# for_BLDC_fan.net
KiCad netlist of a schematic drawn in Altium Designer
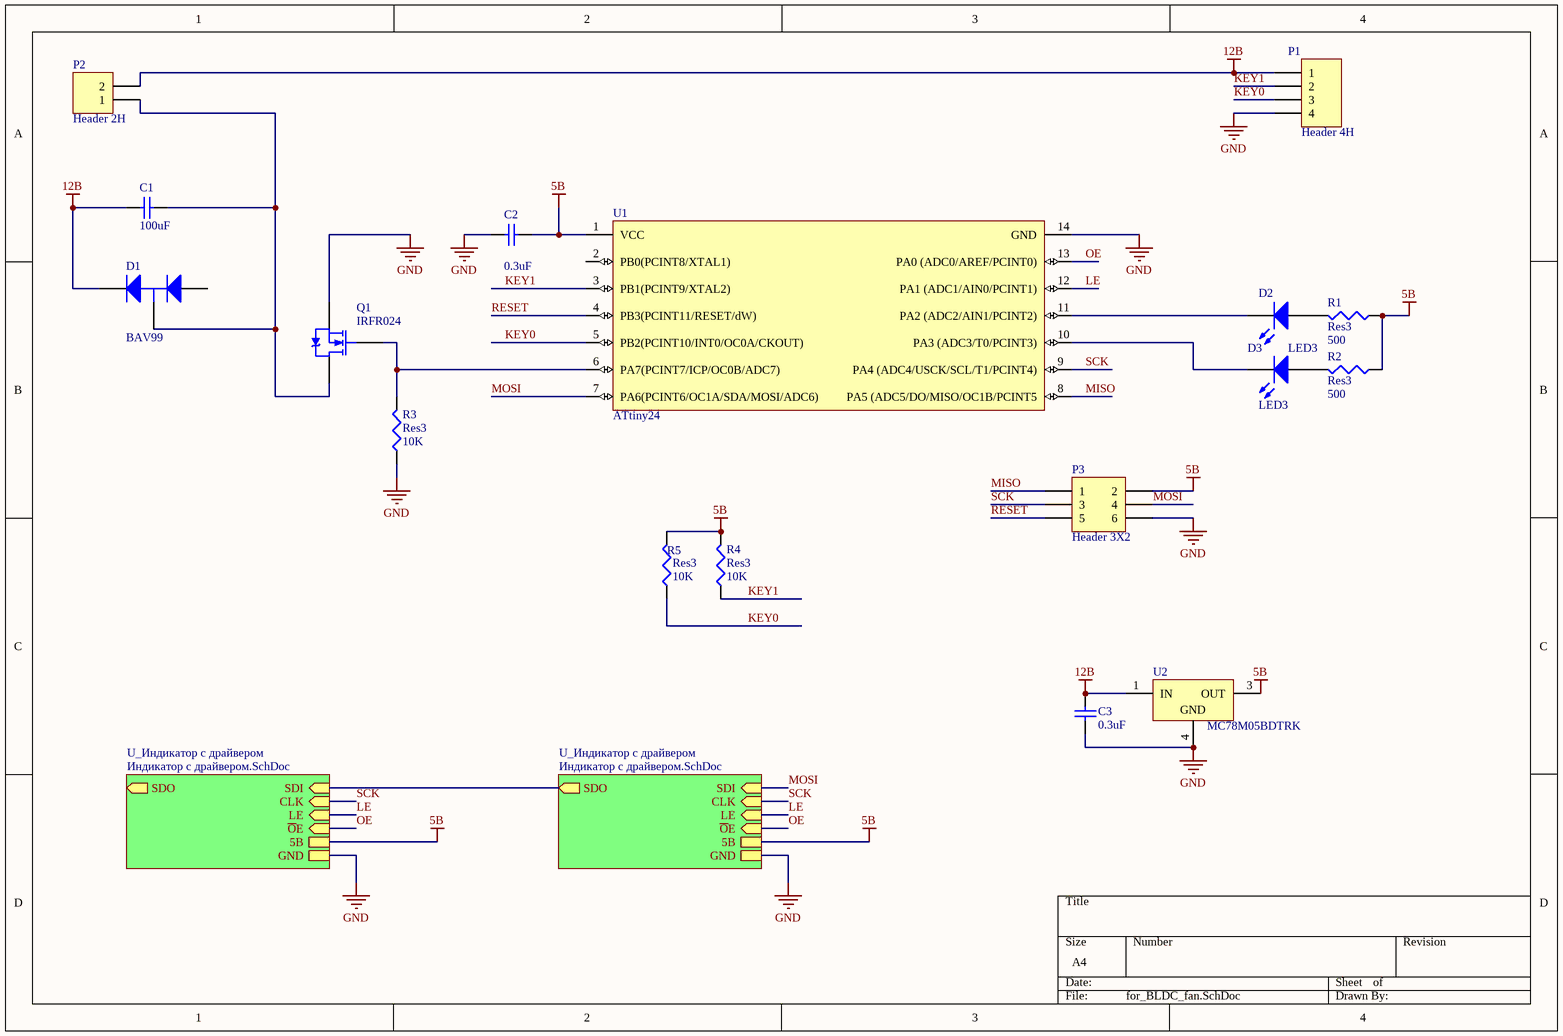
[diagram p0: for_BLDC_fan.SchDoc]

(export (version "E")
  (design (tool "Eeschema 10.0.6"))
  (components
    (comp (ref "C1")
      (value "100uF")
      (footprint "CAPC1608L")
      (description "Capacitor (Semiconductor SIM Model)")
      (fields (field (name "Comment") "Cap Semi") (field (name "PUBLISHER") "Altium Limited"))
      (libsource (lib "Miscellaneous Devices") (part "Cap Semi"))
    )
    (comp (ref "C2")
      (value "0.3uF")
      (footprint "CAPC1608L")
      (description "Capacitor (Semiconductor SIM Model)")
      (fields (field (name "Comment") "Cap Semi") (field (name "PUBLISHER") "Altium Limited"))
      (libsource (lib "Miscellaneous Devices") (part "Cap Semi"))
    )
    (comp (ref "C3")
      (value "0.3uF")
      (footprint "CAPC1608L")
      (description "Capacitor (Semiconductor SIM Model)")
      (fields (field (name "Comment") "Cap Semi") (field (name "PUBLISHER") "Altium Limited"))
      (libsource (lib "Miscellaneous Devices") (part "Cap Semi"))
    )
    (comp (ref "D1")
      (value "BAV99")
      (footprint "SOT-23")
      (description "Silicon Switching Diode Array for High-Speed Switching")
      (fields (field (name "PUBLISHER") "Altium Limited"))
      (libsource (lib "Infineon Discrete Diode") (part "BAV99"))
    )
    (comp (ref "D2")
      (value "LED3")
      (footprint "DSO-C2/D5.6")
      (description "Typical BLUE SiC LED")
      (fields (field (name "PUBLISHER") "Altium Limited"))
      (libsource (lib "Miscellaneous Devices") (part "LED3"))
    )
    (comp (ref "D3")
      (value "LED3")
      (footprint "DSO-C2/D5.6")
      (description "Typical BLUE SiC LED")
      (fields (field (name "PUBLISHER") "Altium Limited"))
      (libsource (lib "Miscellaneous Devices") (part "LED3"))
    )
    (comp (ref "P1")
      (value "Header 4H")
      (footprint "HDR1X4H")
      (description "Header, 4-Pin, Right Angle")
      (fields (field (name "PUBLISHER") "Altium Limited"))
      (libsource (lib "Miscellaneous Connectors") (part "Header 4H"))
    )
    (comp (ref "P2")
      (value "Header 2H")
      (footprint "HDR1X2H")
      (description "Header, 2-Pin, Right Angle")
      (fields (field (name "PUBLISHER") "Altium Limited"))
      (libsource (lib "Miscellaneous Connectors") (part "Header 2H"))
    )
    (comp (ref "P3")
      (value "Header 3X2")
      (footprint "HDR2X3")
      (description "Header, 3-Pin, Dual row")
      (fields (field (name "PUBLISHER") "Altium Limited"))
      (libsource (lib "Miscellaneous Connectors") (part "Header 3X2"))
    )
    (comp (ref "Q1")
      (value "IRFR024")
      (footprint "TO-252AA")
      (description "HEXFET N-Channel Power MOSFET")
      (fields (field (name "PUBLISHER") "Altium Limited"))
      (libsource (lib "IR Discrete MOSFET - Power") (part "IRFR024"))
    )
    (comp (ref "R1")
      (value "Res3")
      (footprint "RESC1608L")
      (description "Resistor")
      (fields (field (name "ALTIUM_VALUE") "500") (field (name "PUBLISHER") "Altium Limited"))
      (libsource (lib "Miscellaneous Devices") (part "Res3"))
    )
    (comp (ref "R2")
      (value "Res3")
      (footprint "RESC1608L")
      (description "Resistor")
      (fields (field (name "ALTIUM_VALUE") "500") (field (name "PUBLISHER") "Altium Limited"))
      (libsource (lib "Miscellaneous Devices") (part "Res3"))
    )
    (comp (ref "R3")
      (value "Res3")
      (footprint "RESC1608L")
      (description "Resistor")
      (fields (field (name "ALTIUM_VALUE") "10K") (field (name "PUBLISHER") "Altium Limited"))
      (libsource (lib "Miscellaneous Devices") (part "Res3"))
    )
    (comp (ref "R4")
      (value "Res3")
      (footprint "RESC1608L")
      (description "Resistor")
      (fields (field (name "ALTIUM_VALUE") "10K") (field (name "PUBLISHER") "Altium Limited"))
      (libsource (lib "Miscellaneous Devices") (part "Res3"))
    )
    (comp (ref "R5")
      (value "Res3")
      (footprint "RESC1608L")
      (description "Resistor")
      (fields (field (name "ALTIUM_VALUE") "10K") (field (name "PUBLISHER") "Altium Limited"))
      (libsource (lib "Miscellaneous Devices") (part "Res3"))
    )
    (comp (ref "U1")
      (value "ATtiny24")
      (footprint "SOIC14_M")
      (description "8-Bit AVR Microcontroller with 1K Byte of Flash Memory")
      (fields (field (name "PUBLISHER") "Altium Limited"))
      (libsource (lib "Integrated_Library1") (part "ATtiny24"))
    )
    (comp (ref "U2")
      (value "MC78M05BDTRK")
      (footprint "369A-13")
      (description "Three-Terminal Medium Current Positive Voltage Regulator")
      (fields (field (name "PUBLISHER") "Altium Limited"))
      (libsource (lib "ON Semi Power Mgt Voltage Regulator") (part "MC78M05BDTRK"))
    )
  )
  (nets
    (net (code "1") (name "/KEY0") (class "Default")
      (node (ref "P1") (pin "3") (pinfunction "3_3") (pintype "passive"))
      (node (ref "R5") (pin "1") (pinfunction "1_1") (pintype "passive"))
      (node (ref "U1") (pin "5") (pinfunction "PB2(PCINT10/INT0/OC0A/CKOUT)_5") (pintype "bidirectional"))
    )
    (net (code "2") (name "/KEY1") (class "Default")
      (node (ref "P1") (pin "2") (pinfunction "2_2") (pintype "passive"))
      (node (ref "R4") (pin "1") (pinfunction "1_1") (pintype "passive"))
      (node (ref "U1") (pin "3") (pinfunction "PB1(PCINT9/XTAL2)_3") (pintype "bidirectional"))
    )
    (net (code "3") (name "/LE") (class "Default")
      (node (ref "U1") (pin "12") (pinfunction "PA1_(ADC1/AIN0/PCINT1)_12") (pintype "bidirectional"))
    )
    (net (code "4") (name "/MISO") (class "Default")
      (node (ref "P3") (pin "1") (pinfunction "1_1") (pintype "passive"))
      (node (ref "U1") (pin "8") (pinfunction "PA5_(ADC5/DO/MISO/OC1B/PCINT5_8") (pintype "bidirectional"))
    )
    (net (code "5") (name "/MOSI") (class "Default")
      (node (ref "P3") (pin "4") (pinfunction "4_4") (pintype "passive"))
      (node (ref "U1") (pin "7") (pinfunction "PA6(PCINT6/OC1A/SDA/MOSI/ADC6)_7") (pintype "bidirectional"))
    )
    (net (code "6") (name "/OE") (class "Default")
      (node (ref "U1") (pin "13") (pinfunction "PA0_(ADC0/AREF/PCINT0)_13") (pintype "bidirectional"))
    )
    (net (code "7") (name "/RESET") (class "Default")
      (node (ref "P3") (pin "5") (pinfunction "5_5") (pintype "passive"))
      (node (ref "U1") (pin "4") (pinfunction "PB3(PCINT11/RESET/dW)_4") (pintype "bidirectional"))
    )
    (net (code "8") (name "/SCK") (class "Default")
      (node (ref "P3") (pin "3") (pinfunction "3_3") (pintype "passive"))
      (node (ref "U1") (pin "9") (pinfunction "PA4_(ADC4/USCK/SCL/T1/PCINT4)_9") (pintype "bidirectional"))
    )
    (net (code "11") (name "5В") (class "Default")
      (node (ref "C2") (pin "2") (pinfunction "2_2") (pintype "passive"))
      (node (ref "P3") (pin "2") (pinfunction "2_2") (pintype "passive"))
      (node (ref "R1") (pin "1") (pinfunction "1_1") (pintype "passive"))
      (node (ref "R2") (pin "1") (pinfunction "1_1") (pintype "passive"))
      (node (ref "R4") (pin "2") (pinfunction "2_2") (pintype "passive"))
      (node (ref "R5") (pin "2") (pinfunction "2_2") (pintype "passive"))
      (node (ref "U1") (pin "1") (pinfunction "VCC_1") (pintype "power_in"))
      (node (ref "U2") (pin "3") (pinfunction "OUT_3") (pintype "power_in"))
    )
    (net (code "12") (name "12B") (class "Default")
      (node (ref "C1") (pin "2") (pinfunction "2_2") (pintype "passive"))
      (node (ref "C3") (pin "2") (pinfunction "2_2") (pintype "passive"))
      (node (ref "D1") (pin "2") (pinfunction "K_2") (pintype "passive"))
      (node (ref "P1") (pin "1") (pinfunction "1_1") (pintype "passive"))
      (node (ref "P2") (pin "2") (pinfunction "2_2") (pintype "passive"))
      (node (ref "U2") (pin "1") (pinfunction "IN_1") (pintype "power_in"))
    )
    (net (code "13") (name "GND") (class "Default")
      (node (ref "C2") (pin "1") (pinfunction "1_1") (pintype "passive"))
      (node (ref "C3") (pin "1") (pinfunction "1_1") (pintype "passive"))
      (node (ref "P1") (pin "4") (pinfunction "4_4") (pintype "passive"))
      (node (ref "P3") (pin "6") (pinfunction "6_6") (pintype "passive"))
      (node (ref "Q1") (pin "3") (pinfunction "S_3") (pintype "passive"))
      (node (ref "R3") (pin "1") (pinfunction "1_1") (pintype "passive"))
      (node (ref "U1") (pin "14") (pinfunction "GND_14") (pintype "power_in"))
      (node (ref "U2") (pin "4") (pinfunction "GND_4") (pintype "power_in"))
    )
    (net (code "14") (name "Net-(D1-C)") (class "Default")
      (node (ref "C1") (pin "1") (pinfunction "1_1") (pintype "passive"))
      (node (ref "D1") (pin "3") (pinfunction "C_3") (pintype "passive"))
      (node (ref "P2") (pin "1") (pinfunction "1_1") (pintype "passive"))
      (node (ref "Q1") (pin "4") (pinfunction "D_4") (pintype "passive"))
    )
    (net (code "15") (name "Net-(D2-A)") (class "Default")
      (node (ref "D2") (pin "1") (pinfunction "A_1") (pintype "passive"))
      (node (ref "R1") (pin "2") (pinfunction "2_2") (pintype "passive"))
    )
    (net (code "16") (name "Net-(D2-K)") (class "Default")
      (node (ref "D2") (pin "2") (pinfunction "K_2") (pintype "passive"))
      (node (ref "U1") (pin "11") (pinfunction "PA2_(ADC2/AIN1/PCINT2)_11") (pintype "bidirectional"))
    )
    (net (code "17") (name "Net-(D3-A)") (class "Default")
      (node (ref "D3") (pin "1") (pinfunction "A_1") (pintype "passive"))
      (node (ref "R2") (pin "2") (pinfunction "2_2") (pintype "passive"))
    )
    (net (code "18") (name "Net-(D3-K)") (class "Default")
      (node (ref "D3") (pin "2") (pinfunction "K_2") (pintype "passive"))
      (node (ref "U1") (pin "10") (pinfunction "PA3_(ADC3/T0/PCINT3)_10") (pintype "bidirectional"))
    )
    (net (code "19") (name "Net-(Q1-G)") (class "Default")
      (node (ref "Q1") (pin "1") (pinfunction "G_1") (pintype "passive"))
      (node (ref "R3") (pin "2") (pinfunction "2_2") (pintype "passive"))
      (node (ref "U1") (pin "6") (pinfunction "PA7(PCINT7/ICP/OC0B/ADC7)_6") (pintype "bidirectional"))
    )
    (net (code "20") (name "unconnected-(D1-A-Pad1)") (class "Default")
      (node (ref "D1") (pin "1") (pinfunction "A_1") (pintype "passive"))
    )
    (net (code "21") (name "unconnected-(U1-PB0(PCINT8{slash}XTAL1)-Pad2)") (class "Default")
      (node (ref "U1") (pin "2") (pinfunction "PB0(PCINT8/XTAL1)_2") (pintype "bidirectional"))
    )
  )
)
